# resistive-probe-adapter_v2.net
KiCad netlist of a schematic drawn in EAGLE
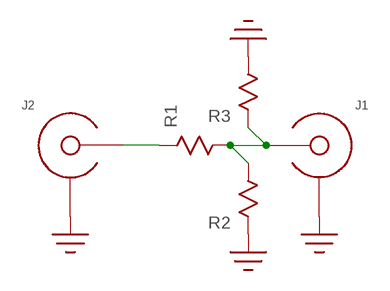
[diagram p0: schematic, sheet 1]

(export (version "E")
  (design (tool "Eeschema 10.0.6"))
  (components
    (comp (ref "J1")
      (value "SMA-EDGE-LAUNCH4020_TAPER")
      (footprint "eagle-import:SMA_EDGE_LAUNCH_2L_4020_TAPER")
      (libsource (lib "eagle-import") (part "SMA-EDGE-LAUNCH4020_TAPER"))
    )
    (comp (ref "J2")
      (value "SMA-EDGE-LAUNCH4020_TAPER")
      (footprint "eagle-import:SMA_EDGE_LAUNCH_2L_4020_TAPER")
      (libsource (lib "eagle-import") (part "SMA-EDGE-LAUNCH4020_TAPER"))
    )
    (comp (ref "R1")
      (value "R0603")
      (footprint "eagle-import:R0603")
      (libsource (lib "eagle-import") (part "R0603"))
    )
    (comp (ref "R2")
      (value "R0603")
      (footprint "eagle-import:R0603")
      (libsource (lib "eagle-import") (part "R0603"))
    )
    (comp (ref "R3")
      (value "R0603")
      (footprint "eagle-import:R0603")
      (libsource (lib "eagle-import") (part "R0603"))
    )
  )
  (nets
    (net (code "1") (name "GND") (class "Default")
      (node (ref "J1") (pin "BOTTOM_GND") (pinfunction "SHIELD_BOTTOM_GND") (pintype "bidirectional"))
      (node (ref "J1") (pin "GND@1") (pinfunction "SHIELD_GND@1") (pintype "bidirectional"))
      (node (ref "J1") (pin "GND@14") (pinfunction "SHIELD_GND@14") (pintype "bidirectional"))
      (node (ref "J1") (pin "GND@15") (pinfunction "SHIELD_GND@15") (pintype "bidirectional"))
      (node (ref "J1") (pin "GND@16") (pinfunction "SHIELD_GND@16") (pintype "bidirectional"))
      (node (ref "J1") (pin "GND@17") (pinfunction "SHIELD_GND@17") (pintype "bidirectional"))
      (node (ref "J1") (pin "GND@2") (pinfunction "SHIELD_GND@2") (pintype "bidirectional"))
      (node (ref "J1") (pin "GND@3") (pinfunction "SHIELD_GND@3") (pintype "bidirectional"))
      (node (ref "J1") (pin "GND@4") (pinfunction "SHIELD_GND@4") (pintype "bidirectional"))
      (node (ref "J1") (pin "GND@5") (pinfunction "SHIELD_GND@5") (pintype "bidirectional"))
      (node (ref "J1") (pin "GND@6") (pinfunction "SHIELD_GND@6") (pintype "bidirectional"))
      (node (ref "J1") (pin "GND@7") (pinfunction "SHIELD_GND@7") (pintype "bidirectional"))
      (node (ref "J1") (pin "GND@8") (pinfunction "SHIELD_GND@8") (pintype "bidirectional"))
      (node (ref "J1") (pin "GND_PAD1") (pinfunction "SHIELD_GND_PAD1") (pintype "bidirectional"))
      (node (ref "J1") (pin "GND_PAD2") (pinfunction "SHIELD_GND_PAD2") (pintype "bidirectional"))
      (node (ref "J1") (pin "P$1") (pinfunction "SHIELD_P$1") (pintype "bidirectional"))
      (node (ref "J1") (pin "P$2") (pinfunction "SHIELD_P$2") (pintype "bidirectional"))
      (node (ref "J2") (pin "BOTTOM_GND") (pinfunction "SHIELD_BOTTOM_GND") (pintype "bidirectional"))
      (node (ref "J2") (pin "GND@1") (pinfunction "SHIELD_GND@1") (pintype "bidirectional"))
      (node (ref "J2") (pin "GND@14") (pinfunction "SHIELD_GND@14") (pintype "bidirectional"))
      (node (ref "J2") (pin "GND@15") (pinfunction "SHIELD_GND@15") (pintype "bidirectional"))
      (node (ref "J2") (pin "GND@16") (pinfunction "SHIELD_GND@16") (pintype "bidirectional"))
      (node (ref "J2") (pin "GND@17") (pinfunction "SHIELD_GND@17") (pintype "bidirectional"))
      (node (ref "J2") (pin "GND@2") (pinfunction "SHIELD_GND@2") (pintype "bidirectional"))
      (node (ref "J2") (pin "GND@3") (pinfunction "SHIELD_GND@3") (pintype "bidirectional"))
      (node (ref "J2") (pin "GND@4") (pinfunction "SHIELD_GND@4") (pintype "bidirectional"))
      (node (ref "J2") (pin "GND@5") (pinfunction "SHIELD_GND@5") (pintype "bidirectional"))
      (node (ref "J2") (pin "GND@6") (pinfunction "SHIELD_GND@6") (pintype "bidirectional"))
      (node (ref "J2") (pin "GND@7") (pinfunction "SHIELD_GND@7") (pintype "bidirectional"))
      (node (ref "J2") (pin "GND@8") (pinfunction "SHIELD_GND@8") (pintype "bidirectional"))
      (node (ref "J2") (pin "GND_PAD1") (pinfunction "SHIELD_GND_PAD1") (pintype "bidirectional"))
      (node (ref "J2") (pin "GND_PAD2") (pinfunction "SHIELD_GND_PAD2") (pintype "bidirectional"))
      (node (ref "J2") (pin "P$1") (pinfunction "SHIELD_P$1") (pintype "bidirectional"))
      (node (ref "J2") (pin "P$2") (pinfunction "SHIELD_P$2") (pintype "bidirectional"))
      (node (ref "R2") (pin "P$1") (pinfunction "P$3_P$1") (pintype "bidirectional"))
      (node (ref "R3") (pin "P$2") (pinfunction "P$4_P$2") (pintype "bidirectional"))
    )
    (net (code "2") (name "Net-(J1-CENTER)") (class "Default")
      (node (ref "J1") (pin "CENTER@1") (pinfunction "CENTER_CENTER@1") (pintype "bidirectional"))
      (node (ref "R1") (pin "P$2") (pinfunction "P$4_P$2") (pintype "bidirectional"))
      (node (ref "R2") (pin "P$2") (pinfunction "P$4_P$2") (pintype "bidirectional"))
      (node (ref "R3") (pin "P$1") (pinfunction "P$3_P$1") (pintype "bidirectional"))
    )
    (net (code "3") (name "Net-(J2-CENTER)") (class "Default")
      (node (ref "J2") (pin "CENTER@1") (pinfunction "CENTER_CENTER@1") (pintype "bidirectional"))
      (node (ref "R1") (pin "P$1") (pinfunction "P$3_P$1") (pintype "bidirectional"))
    )
  )
)
